# POWERSYSTEM.net
KiCad netlist of a schematic drawn in Altium Designer
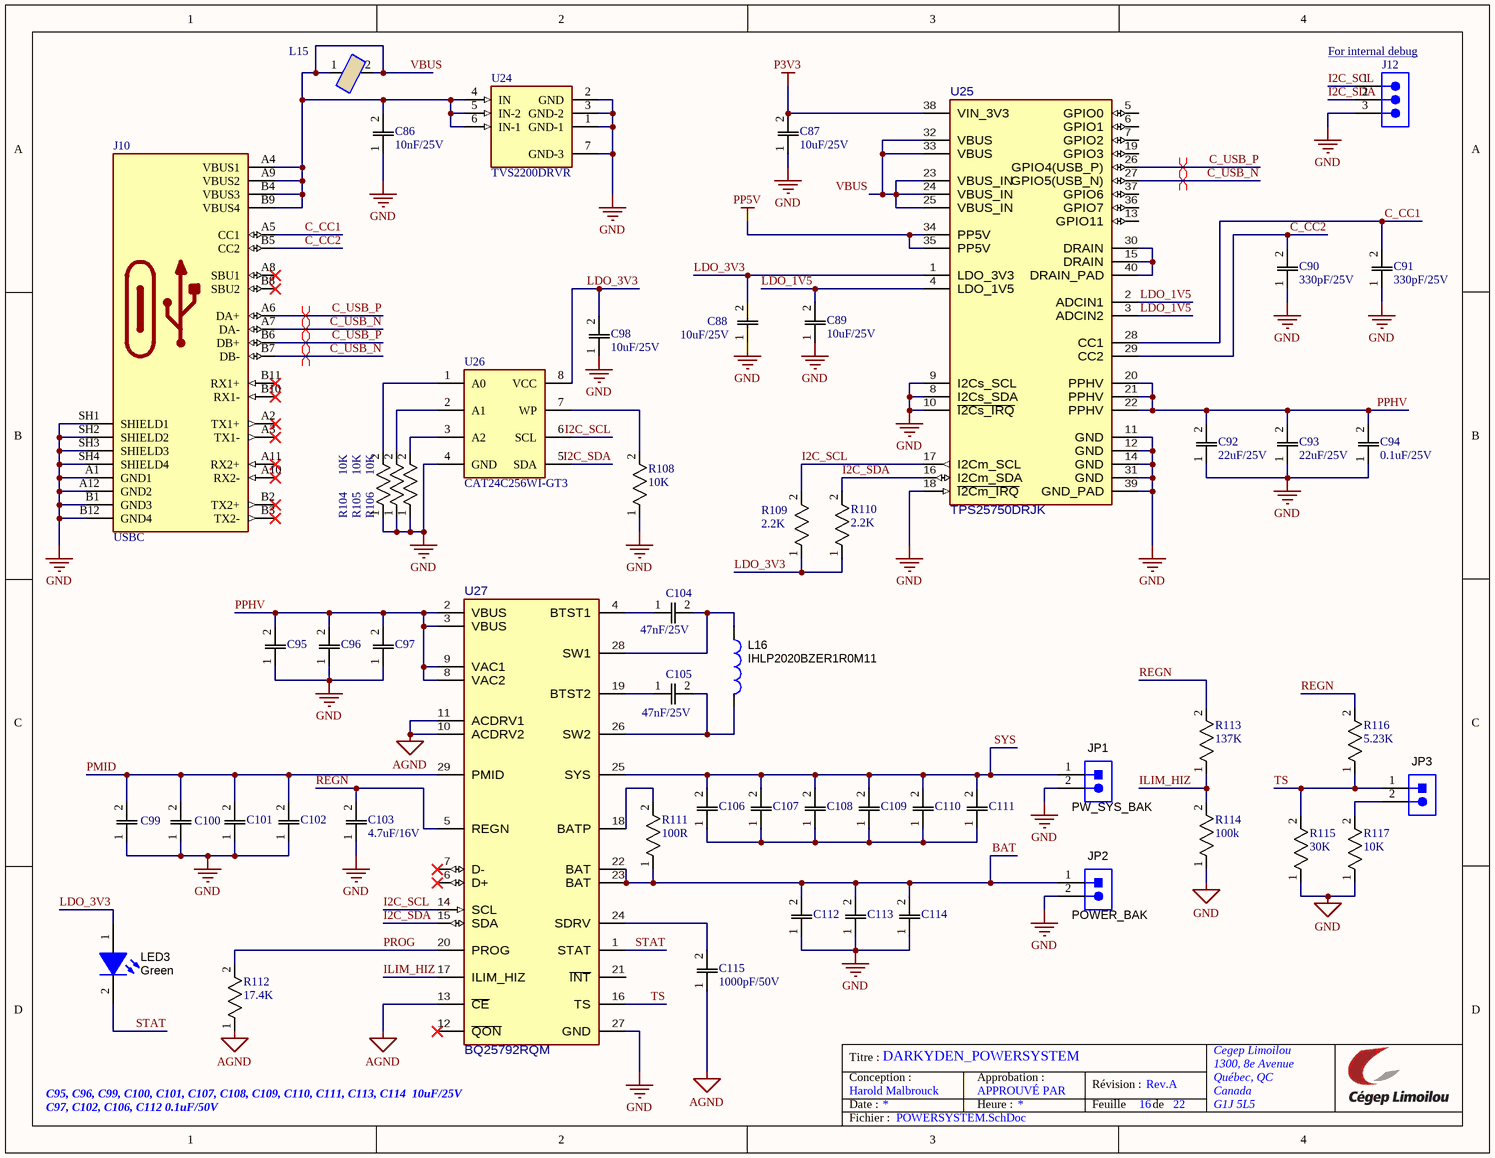
[diagram p0: POWERSYSTEM.SchDoc]

(export (version "E")
  (design (tool "Eeschema 10.0.6"))
  (components
    (comp (ref "C86")
      (value "10nF/25V")
      (footprint "CAPC220145_88N_KEM")
      (description "No Description Available")
      (libsource (lib "Capacitor_0805") (part "Capacitor_0805"))
    )
    (comp (ref "C87")
      (value "10uF/25V")
      (footprint "CAPC220145_88N_KEM")
      (description "No Description Available")
      (libsource (lib "Capacitor_0805") (part "Capacitor_0805"))
    )
    (comp (ref "C88")
      (value "10uF/25V")
      (footprint "CAPC220145_88N_KEM")
      (description "No Description Available")
      (libsource (lib "Capacitor_0805") (part "Capacitor_0805"))
    )
    (comp (ref "C89")
      (value "10uF/25V")
      (footprint "CAPC220145_88N_KEM")
      (description "No Description Available")
      (libsource (lib "Capacitor_0805") (part "Capacitor_0805"))
    )
    (comp (ref "C90")
      (value "330pF/25V")
      (footprint "CAPC220145_88N_KEM")
      (description "No Description Available")
      (libsource (lib "Capacitor_0805") (part "Capacitor_0805"))
    )
    (comp (ref "C91")
      (value "330pF/25V")
      (footprint "CAPC220145_88N_KEM")
      (description "No Description Available")
      (libsource (lib "Capacitor_0805") (part "Capacitor_0805"))
    )
    (comp (ref "C92")
      (value "22uF/25V")
      (footprint "CAPC220145_88N_KEM")
      (description "No Description Available")
      (libsource (lib "Capacitor_0805") (part "Capacitor_0805"))
    )
    (comp (ref "C93")
      (value "22uF/25V")
      (footprint "CAPC220145_88N_KEM")
      (description "No Description Available")
      (libsource (lib "Capacitor_0805") (part "Capacitor_0805"))
    )
    (comp (ref "C94")
      (value "0.1uF/25V")
      (footprint "CAPC220145_88N_KEM")
      (description "No Description Available")
      (libsource (lib "Capacitor_0805") (part "Capacitor_0805"))
    )
    (comp (ref "C95")
      (value "10uF/25V")
      (footprint "CAPC220145_88N_KEM")
      (description "No Description Available")
      (libsource (lib "Capacitor_0805") (part "Capacitor_0805"))
    )
    (comp (ref "C96")
      (value "10uF/25V")
      (footprint "CAPC220145_88N_KEM")
      (description "No Description Available")
      (libsource (lib "Capacitor_0805") (part "Capacitor_0805"))
    )
    (comp (ref "C97")
      (value "0.1uF/50V")
      (footprint "CAPC220145_88N_KEM")
      (description "No Description Available")
      (libsource (lib "Capacitor_0805") (part "Capacitor_0805"))
    )
    (comp (ref "C98")
      (value "10uF/25V")
      (footprint "CAPC220145_88N_KEM")
      (description "No Description Available")
      (libsource (lib "Capacitor_0805") (part "Capacitor_0805"))
    )
    (comp (ref "C99")
      (value "10uF/25V")
      (footprint "CAPC220145_88N_KEM")
      (description "No Description Available")
      (libsource (lib "Capacitor_0805") (part "Capacitor_0805"))
    )
    (comp (ref "C100")
      (value "10uF/25V")
      (footprint "CAPC220145_88N_KEM")
      (description "No Description Available")
      (libsource (lib "Capacitor_0805") (part "Capacitor_0805"))
    )
    (comp (ref "C101")
      (value "10uF/25V")
      (footprint "CAPC220145_88N_KEM")
      (description "No Description Available")
      (libsource (lib "Capacitor_0805") (part "Capacitor_0805"))
    )
    (comp (ref "C102")
      (value "0.1uF/50V")
      (footprint "CAPC220145_88N_KEM")
      (description "No Description Available")
      (libsource (lib "Capacitor_0805") (part "Capacitor_0805"))
    )
    (comp (ref "C103")
      (value "4.7uF/16V")
      (footprint "CAPC220145_88N_KEM")
      (description "No Description Available")
      (libsource (lib "Capacitor_0805") (part "Capacitor_0805"))
    )
    (comp (ref "C104")
      (value "47nF/25V")
      (footprint "CAPC220145_88N_KEM")
      (description "No Description Available")
      (libsource (lib "Capacitor_0805") (part "Capacitor_0805"))
    )
    (comp (ref "C105")
      (value "47nF/25V")
      (footprint "CAPC220145_88N_KEM")
      (description "No Description Available")
      (libsource (lib "Capacitor_0805") (part "Capacitor_0805"))
    )
    (comp (ref "C106")
      (value "0.1uF/50V")
      (footprint "CAPC220145_88N_KEM")
      (description "No Description Available")
      (libsource (lib "Capacitor_0805") (part "Capacitor_0805"))
    )
    (comp (ref "C107")
      (value "10uF/25V")
      (footprint "CAPC220145_88N_KEM")
      (description "No Description Available")
      (libsource (lib "Capacitor_0805") (part "Capacitor_0805"))
    )
    (comp (ref "C108")
      (value "10uF/25V")
      (footprint "CAPC220145_88N_KEM")
      (description "No Description Available")
      (libsource (lib "Capacitor_0805") (part "Capacitor_0805"))
    )
    (comp (ref "C109")
      (value "10uF/25V")
      (footprint "CAPC220145_88N_KEM")
      (description "No Description Available")
      (libsource (lib "Capacitor_0805") (part "Capacitor_0805"))
    )
    (comp (ref "C110")
      (value "10uF/25V")
      (footprint "CAPC220145_88N_KEM")
      (description "No Description Available")
      (libsource (lib "Capacitor_0805") (part "Capacitor_0805"))
    )
    (comp (ref "C111")
      (value "10uF/25V")
      (footprint "CAPC220145_88N_KEM")
      (description "No Description Available")
      (libsource (lib "Capacitor_0805") (part "Capacitor_0805"))
    )
    (comp (ref "C112")
      (value "0.1uF/50V")
      (footprint "CAPC220145_88N_KEM")
      (description "No Description Available")
      (libsource (lib "Capacitor_0805") (part "Capacitor_0805"))
    )
    (comp (ref "C113")
      (value "10uF/25V")
      (footprint "CAPC220145_88N_KEM")
      (description "No Description Available")
      (libsource (lib "Capacitor_0805") (part "Capacitor_0805"))
    )
    (comp (ref "C114")
      (value "10uF/25V")
      (footprint "CAPC220145_88N_KEM")
      (description "No Description Available")
      (libsource (lib "Capacitor_0805") (part "Capacitor_0805"))
    )
    (comp (ref "C115")
      (value "1000pF/50V")
      (footprint "CAPC220145_88N_KEM")
      (description "No Description Available")
      (libsource (lib "Capacitor_0805") (part "Capacitor_0805"))
    )
    (comp (ref "J10")
      (value "USBC")
      (footprint "MOLEX_2012670005")
      (fields (field (name "MF") "Molex") (field (name "MP") "2012670005"))
      (libsource (lib "USBC") (part "USBC"))
    )
    (comp (ref "J12")
      (value "61300311121")
      (footprint "61300311121")
      (description "WR-PHD Pin Header, THT, Vertical, pitch 2.54mm, 1 Row, 3P")
      (fields (field (name "MANUFACTURER") "Wurth Elektronik"))
      (libsource (lib "Header") (part "61300311121"))
    )
    (comp (ref "JP1")
      (value "PW_SYS_BAK")
      (footprint "61300211121")
      (description "Header, 100mil, 2x1, Tin, TH")
      (fields
        (field (name "PARTNUMBER") "PEC02SAAN")
        (field (name "MANUFACTURER") "Sullins Connector Solutions")
        (field (name "PUBLISHER") "Texas Instruments")
      )
      (libsource (lib "texas_instrument_power") (part "Header_2x1"))
    )
    (comp (ref "JP2")
      (value "POWER_BAK")
      (footprint "61300211121")
      (description "Header, 100mil, 2x1, Tin, TH")
      (fields
        (field (name "PARTNUMBER") "PEC02SAAN")
        (field (name "MANUFACTURER") "Sullins Connector Solutions")
        (field (name "PUBLISHER") "Texas Instruments")
      )
      (libsource (lib "texas_instrument_power") (part "Header_2x1"))
    )
    (comp (ref "JP3")
      (value "TS")
      (footprint "61300211121")
      (description "Header, 100mil, 2x1, Tin, TH")
      (fields
        (field (name "PARTNUMBER") "PEC02SAAN")
        (field (name "MANUFACTURER") "Sullins Connector Solutions")
        (field (name "PUBLISHER") "Texas Instruments")
      )
      (libsource (lib "texas_instrument_power") (part "Header_2x1"))
    )
    (comp (ref "L15")
      (value "FBMJ2125HM210NT")
      (footprint "INDC2012X105N")
      (description "Ferrite Beads Power Chip 21Ohm 30% 100MHz 6A 0.004Ohm DCR 0805 Automotive T/R")
      (fields
        (field (name "MANUFACTURER") "Taiyo Yuden")
        (field (name "MOUSER PART NUMBER") "963-FBMJ2125HM210NT")
      )
      (libsource (lib "SamacSys") (part "FBMJ2125HM210NT"))
    )
    (comp (ref "L16")
      (value "IHLP2020BZER1R0M11")
      (footprint "IHLP-2020BZ")
      (description "Inductor, Shielded Drum Core, Powdered Iron, 1 uH, 7 A, 0.0181 ohm, SMD")
      (fields (field (name "MANUFACTURER") "Vishay-Dale") (field (name "PUBLISHER") "Texas Instruments"))
      (libsource (lib "texas_instrument_power") (part "IHLP2020BZER1R0M11"))
    )
    (comp (ref "LED3")
      (value "Green")
      (footprint "LED_LTST-C190")
      (description "LED, Green, SMD")
      (fields (field (name "MANUFACTURER") "Lite-On") (field (name "PARTNUMBER") "LTST-C190GKT"))
      (libsource (lib "PD_BQ_Ref_Design") (part "LED_Gr_SMD"))
    )
    (comp (ref "R104")
      (value "10K")
      (footprint "SamacSys:ERJ3EKF1000V")
      (description "10K Ohm 5% Res Thick Film 0603  0.1W(1/10W) ±200ppm/C Pad SMD Automotive T/R")
      (fields
        (field (name "MANUFACTURER_PART_NUMBER") "ERJ-3GEYJ103V")
        (field (name "MOUSER PART NUMBER") "667-ERJ-3GEYJ103V")
      )
      (libsource (lib "SamacSys") (part "ERJ-3GEYJ103V"))
    )
    (comp (ref "R105")
      (value "10K")
      (footprint "SamacSys:ERJ3EKF1000V")
      (description "10K Ohm 5% Res Thick Film 0603  0.1W(1/10W) ±200ppm/C Pad SMD Automotive T/R")
      (fields
        (field (name "MANUFACTURER_PART_NUMBER") "ERJ-3GEYJ103V")
        (field (name "MOUSER PART NUMBER") "667-ERJ-3GEYJ103V")
      )
      (libsource (lib "SamacSys") (part "ERJ-3GEYJ103V"))
    )
    (comp (ref "R106")
      (value "10K")
      (footprint "SamacSys:ERJ3EKF1000V")
      (description "10K Ohm 5% Res Thick Film 0603  0.1W(1/10W) ±200ppm/C Pad SMD Automotive T/R")
      (fields
        (field (name "MANUFACTURER_PART_NUMBER") "ERJ-3GEYJ103V")
        (field (name "MOUSER PART NUMBER") "667-ERJ-3GEYJ103V")
      )
      (libsource (lib "SamacSys") (part "ERJ-3GEYJ103V"))
    )
    (comp (ref "R108")
      (value "10K")
      (footprint "SamacSys:ERJ3EKF1000V")
      (description "10K Ohm 5% Res Thick Film 0603  0.1W(1/10W) ±200ppm/C Pad SMD Automotive T/R")
      (fields
        (field (name "MANUFACTURER_PART_NUMBER") "ERJ-3GEYJ103V")
        (field (name "MOUSER PART NUMBER") "667-ERJ-3GEYJ103V")
      )
      (libsource (lib "SamacSys") (part "ERJ-3GEYJ103V"))
    )
    (comp (ref "R109")
      (value "2.2K")
      (footprint "SamacSys:ERJ3EKF1000V")
      (description "2.2 kOhm, ï¿½ 5%, 100 mW, 0603 [1608 Metric], Thick Film, General Purpose")
      (fields
        (field (name "MANUFACTURER_PART_NUMBER") "ERJ-3GEYJ222V")
        (field (name "MOUSER PART NUMBER") "667-ERJ-3GEYJ222V")
      )
      (libsource (lib "SamacSys") (part "ERJ-3GEYJ222V"))
    )
    (comp (ref "R110")
      (value "2.2K")
      (footprint "SamacSys:ERJ3EKF1000V")
      (description "2.2 kOhm, ï¿½ 5%, 100 mW, 0603 [1608 Metric], Thick Film, General Purpose")
      (fields
        (field (name "MANUFACTURER_PART_NUMBER") "ERJ-3GEYJ222V")
        (field (name "MOUSER PART NUMBER") "667-ERJ-3GEYJ222V")
      )
      (libsource (lib "SamacSys") (part "ERJ-3GEYJ222V"))
    )
    (comp (ref "R111")
      (value "100R")
      (footprint "SamacSys:RESC1608X55N")
      (description "100 Ohm 1% 1/10W 0603 ±100ppm/°C Molded SMD Punched Carrier T/R")
      (fields
        (field (name "MANUFACTURER_PART_NUMBER") "ERJ-3EKF1000V")
        (field (name "MOUSER PART NUMBER") "667-ERJ-3EKF1000V")
      )
      (libsource (lib "SamacSys") (part "ERJ-3EKF1000V"))
    )
    (comp (ref "R112")
      (value "17.4K")
      (footprint "SamacSys:RESC1608X55N")
      (description "17.4K Ohm 1% 1/10W +/-100ppm/ßC Molded Res Thick Film 0603  SMD Punched Carrier T/R")
      (fields
        (field (name "MANUFACTURER_PART_NUMBER") "ERJ-3EKF1742V")
        (field (name "MOUSER PART NUMBER") "667-ERJ-3EKF1742V")
      )
      (libsource (lib "SamacSys") (part "ERJ-3EKF1742V"))
    )
    (comp (ref "R113")
      (value "137K")
      (footprint "SamacSys:RESC1608X55N")
      (description "137K Ohm 1% 1/10W Res Thick Film 0603 ±100ppm/°C SMD Punched Carrier T/R")
      (fields
        (field (name "MANUFACTURER_PART_NUMBER") "ERJ-3EKF1373V")
        (field (name "MOUSER PART NUMBER") "667-ERJ-3EKF1373V")
      )
      (libsource (lib "SamacSys") (part "ERJ-3EKF1373V"))
    )
    (comp (ref "R114")
      (value "100k")
      (footprint "SamacSys:ERJ3EKF1000V")
      (description "100K Ohm 5%  Res Thick Film 0603 1/10W +/-200ppm/ßC Molded SMD Punched Carrier T/R")
      (fields
        (field (name "MANUFACTURER_PART_NUMBER") "ERJ-3GEYJ104V")
        (field (name "MOUSER PART NUMBER") "667-ERJ-3GEYJ104V")
      )
      (libsource (lib "SamacSys") (part "ERJ-3GEYJ104V"))
    )
    (comp (ref "R115")
      (value "30K")
      (footprint "SamacSys:ERJ3EKF1000V")
      (description "30K Ohm 5% 0.1W(1/10W) +/-200ppm/ßC Res Thick Film 0603  SMD Automotive T/R")
      (fields
        (field (name "MANUFACTURER_PART_NUMBER") "ERJ-3GEYJ303V")
        (field (name "MOUSER PART NUMBER") "667-ERJ-3GEYJ303V")
      )
      (libsource (lib "SamacSys") (part "ERJ-3GEYJ303V"))
    )
    (comp (ref "R116")
      (value "5.23K")
      (footprint "SamacSys:RESC1608X55N")
      (description "5.23K Ohm 1% 1/10W Res Thick Film 0603+/-100ppm/ßC Molded SMD Punched Carrier T/R")
      (fields
        (field (name "MANUFACTURER_PART_NUMBER") "ERJ-3EKF5231V")
        (field (name "MOUSER PART NUMBER") "667-ERJ-3EKF5231V")
      )
      (libsource (lib "SamacSys") (part "ERJ-3EKF5231V"))
    )
    (comp (ref "R117")
      (value "10K")
      (footprint "SamacSys:ERJ3EKF1000V")
      (description "10K Ohm 5% Res Thick Film 0603  0.1W(1/10W) ±200ppm/C Pad SMD Automotive T/R")
      (fields
        (field (name "MANUFACTURER_PART_NUMBER") "ERJ-3GEYJ103V")
        (field (name "MOUSER PART NUMBER") "667-ERJ-3GEYJ103V")
      )
      (libsource (lib "SamacSys") (part "ERJ-3GEYJ103V"))
    )
    (comp (ref "U24")
      (value "TVS2200DRVR")
      (footprint "SON65P200X200X80-7N")
      (description "ESD Suppressors / TVS Diodes 22V flat-clamp surge protection device 6-WSON -40 to 125")
      (fields (field (name "MF") "Texas Instruments"))
      (libsource (lib "TVS2200") (part "TVS2200DRVR"))
    )
    (comp (ref "U25")
      (value "TPS25750DRJK")
      (footprint "RJK0038B-C01-MFG")
      (description "USB Type-C and USB PD Controller with Integrated Power Switches Optimized for Power Applications")
      (fields (field (name "MANUFACTURER") "Texas Instruments"))
      (libsource (lib "PD_BQ_Ref_Design") (part "TPS25750DRJK"))
    )
    (comp (ref "U26")
      (value "CAT24C256WI-GT3")
      (footprint "SamacSys:SOIC127P600X175-8N")
      (description "EEPROM Memory IC 256Kbit I2C 1 MHz 500 ns 8-SOIC")
      (fields (field (name "MOUSER PART NUMBER") "698-CAT24C256WI-GT3"))
      (libsource (lib "SamacSys") (part "CAT24C256WI-GT3"))
    )
    (comp (ref "U27")
      (value "BQ25792RQM")
      (footprint "RQM0029A-MFG")
      (description "BQ2579x HotRod")
      (fields (field (name "MANUFACTURER") "Texas Instruments"))
      (libsource (lib "PD_BQ_Ref_Design") (part "BQ2579x"))
    )
  )
  (nets
    (net (code "1") (name "/BAT") (class "Default")
      (node (ref "C112") (pin "2") (pinfunction "2_2") (pintype "passive"))
      (node (ref "C113") (pin "2") (pinfunction "2_2") (pintype "passive"))
      (node (ref "C114") (pin "2") (pinfunction "2_2") (pintype "passive"))
      (node (ref "JP2") (pin "1") (pinfunction "1_1") (pintype "passive"))
      (node (ref "R111") (pin "1") (pinfunction "1_1") (pintype "passive"))
      (node (ref "U27") (pin "22") (pinfunction "BAT_22") (pintype "passive"))
      (node (ref "U27") (pin "23") (pinfunction "BAT_23") (pintype "passive"))
    )
    (net (code "2") (name "/C_CC1") (class "Default")
      (node (ref "C91") (pin "2") (pinfunction "2_2") (pintype "passive"))
      (node (ref "J10") (pin "A5") (pinfunction "CC1_A5") (pintype "bidirectional"))
      (node (ref "U25") (pin "28") (pinfunction "CC1_28") (pintype "passive"))
    )
    (net (code "3") (name "/C_CC2") (class "Default")
      (node (ref "C90") (pin "2") (pinfunction "2_2") (pintype "passive"))
      (node (ref "J10") (pin "B5") (pinfunction "CC2_B5") (pintype "bidirectional"))
      (node (ref "U25") (pin "29") (pinfunction "CC2_29") (pintype "passive"))
    )
    (net (code "4") (name "/C_USB_N") (class "Default")
      (node (ref "J10") (pin "A7") (pinfunction "DA-_A7") (pintype "bidirectional"))
      (node (ref "J10") (pin "B7") (pinfunction "DB-_B7") (pintype "bidirectional"))
      (node (ref "U25") (pin "27") (pinfunction "GPIO5(USB_N)_27") (pintype "bidirectional"))
    )
    (net (code "5") (name "/C_USB_P") (class "Default")
      (node (ref "J10") (pin "A6") (pinfunction "DA+_A6") (pintype "bidirectional"))
      (node (ref "J10") (pin "B6") (pinfunction "DB+_B6") (pintype "bidirectional"))
      (node (ref "U25") (pin "26") (pinfunction "GPIO4(USB_P)_26") (pintype "bidirectional"))
    )
    (net (code "6") (name "/I2C_SCL") (class "Default")
      (node (ref "J12") (pin "1") (pinfunction "1_1") (pintype "passive"))
      (node (ref "R109") (pin "2") (pinfunction "2_2") (pintype "passive"))
      (node (ref "U25") (pin "17") (pinfunction "I2Cm_SCL_17") (pintype "output"))
      (node (ref "U26") (pin "6") (pinfunction "SCL_6") (pintype "passive"))
      (node (ref "U27") (pin "14") (pinfunction "SCL_14") (pintype "input"))
    )
    (net (code "7") (name "/I2C_SDA") (class "Default")
      (node (ref "J12") (pin "2") (pinfunction "2_2") (pintype "passive"))
      (node (ref "R110") (pin "2") (pinfunction "2_2") (pintype "passive"))
      (node (ref "U25") (pin "16") (pinfunction "I2Cm_SDA_16") (pintype "bidirectional"))
      (node (ref "U26") (pin "5") (pinfunction "SDA_5") (pintype "passive"))
      (node (ref "U27") (pin "15") (pinfunction "SDA_15") (pintype "bidirectional"))
    )
    (net (code "8") (name "/ILIM_HIZ") (class "Default")
      (node (ref "R113") (pin "1") (pinfunction "1_1") (pintype "passive"))
      (node (ref "R114") (pin "2") (pinfunction "2_2") (pintype "passive"))
      (node (ref "U27") (pin "17") (pinfunction "ILIM_HIZ_17") (pintype "passive"))
    )
    (net (code "9") (name "/LDO_1V5") (class "Default")
      (node (ref "C89") (pin "2") (pinfunction "2_2") (pintype "passive"))
      (node (ref "U25") (pin "2") (pinfunction "ADCIN1_2") (pintype "passive"))
      (node (ref "U25") (pin "3") (pinfunction "ADCIN2_3") (pintype "passive"))
      (node (ref "U25") (pin "4") (pinfunction "LDO_1V5_4") (pintype "passive"))
    )
    (net (code "10") (name "/LDO_3V3") (class "Default")
      (node (ref "C88") (pin "2") (pinfunction "2_2") (pintype "passive"))
      (node (ref "C98") (pin "2") (pinfunction "2_2") (pintype "passive"))
      (node (ref "LED3") (pin "1") (pinfunction "A_1") (pintype "passive"))
      (node (ref "R109") (pin "1") (pinfunction "1_1") (pintype "passive"))
      (node (ref "R110") (pin "1") (pinfunction "1_1") (pintype "passive"))
      (node (ref "U25") (pin "1") (pinfunction "LDO_3V3_1") (pintype "passive"))
      (node (ref "U26") (pin "8") (pinfunction "VCC_8") (pintype "passive"))
    )
    (net (code "11") (name "/PMID") (class "Default")
      (node (ref "C100") (pin "2") (pinfunction "2_2") (pintype "passive"))
      (node (ref "C101") (pin "2") (pinfunction "2_2") (pintype "passive"))
      (node (ref "C102") (pin "2") (pinfunction "2_2") (pintype "passive"))
      (node (ref "C99") (pin "2") (pinfunction "2_2") (pintype "passive"))
      (node (ref "U27") (pin "29") (pinfunction "PMID_29") (pintype "passive"))
    )
    (net (code "12") (name "/PPHV") (class "Default")
      (node (ref "C92") (pin "2") (pinfunction "2_2") (pintype "passive"))
      (node (ref "C93") (pin "2") (pinfunction "2_2") (pintype "passive"))
      (node (ref "C94") (pin "2") (pinfunction "2_2") (pintype "passive"))
      (node (ref "C95") (pin "2") (pinfunction "2_2") (pintype "passive"))
      (node (ref "C96") (pin "2") (pinfunction "2_2") (pintype "passive"))
      (node (ref "C97") (pin "2") (pinfunction "2_2") (pintype "passive"))
      (node (ref "U25") (pin "20") (pinfunction "PPHV_20") (pintype "passive"))
      (node (ref "U25") (pin "21") (pinfunction "PPHV_21") (pintype "passive"))
      (node (ref "U25") (pin "22") (pinfunction "PPHV_22") (pintype "passive"))
      (node (ref "U27") (pin "2") (pinfunction "VBUS_2") (pintype "power_in"))
      (node (ref "U27") (pin "3") (pinfunction "VBUS_3") (pintype "power_in"))
      (node (ref "U27") (pin "8") (pinfunction "VAC2_8") (pintype "power_in"))
      (node (ref "U27") (pin "9") (pinfunction "VAC1_9") (pintype "power_in"))
    )
    (net (code "13") (name "/PROG") (class "Default")
      (node (ref "R112") (pin "2") (pinfunction "2_2") (pintype "passive"))
      (node (ref "U27") (pin "20") (pinfunction "PROG_20") (pintype "passive"))
    )
    (net (code "14") (name "/REGN") (class "Default")
      (node (ref "C103") (pin "2") (pinfunction "2_2") (pintype "passive"))
      (node (ref "R113") (pin "2") (pinfunction "2_2") (pintype "passive"))
      (node (ref "R116") (pin "2") (pinfunction "2_2") (pintype "passive"))
      (node (ref "U27") (pin "5") (pinfunction "REGN_5") (pintype "passive"))
    )
    (net (code "15") (name "/STAT") (class "Default")
      (node (ref "LED3") (pin "2") (pinfunction "K_2") (pintype "passive"))
      (node (ref "U27") (pin "1") (pinfunction "STAT_1") (pintype "passive"))
    )
    (net (code "16") (name "/SYS") (class "Default")
      (node (ref "C106") (pin "2") (pinfunction "2_2") (pintype "passive"))
      (node (ref "C107") (pin "2") (pinfunction "2_2") (pintype "passive"))
      (node (ref "C108") (pin "2") (pinfunction "2_2") (pintype "passive"))
      (node (ref "C109") (pin "2") (pinfunction "2_2") (pintype "passive"))
      (node (ref "C110") (pin "2") (pinfunction "2_2") (pintype "passive"))
      (node (ref "C111") (pin "2") (pinfunction "2_2") (pintype "passive"))
      (node (ref "JP1") (pin "1") (pinfunction "1_1") (pintype "passive"))
      (node (ref "U27") (pin "25") (pinfunction "SYS_25") (pintype "passive"))
    )
    (net (code "17") (name "/TS") (class "Default")
      (node (ref "JP3") (pin "1") (pinfunction "1_1") (pintype "passive"))
      (node (ref "R115") (pin "2") (pinfunction "2_2") (pintype "passive"))
      (node (ref "R116") (pin "1") (pinfunction "1_1") (pintype "passive"))
      (node (ref "U27") (pin "16") (pinfunction "TS_16") (pintype "passive"))
    )
    (net (code "18") (name "/VBUS") (class "Default")
      (node (ref "C86") (pin "2") (pinfunction "2_2") (pintype "passive"))
      (node (ref "J10") (pin "A4") (pinfunction "VBUS1_A4") (pintype "power_in"))
      (node (ref "J10") (pin "A9") (pinfunction "VBUS2_A9") (pintype "power_in"))
      (node (ref "J10") (pin "B4") (pinfunction "VBUS3_B4") (pintype "power_in"))
      (node (ref "J10") (pin "B9") (pinfunction "VBUS4_B9") (pintype "power_in"))
      (node (ref "L15") (pin "1") (pinfunction "1_1") (pintype "passive"))
      (node (ref "L15") (pin "2") (pinfunction "2_2") (pintype "passive"))
      (node (ref "U24") (pin "4") (pinfunction "IN_4") (pintype "input"))
      (node (ref "U24") (pin "5") (pinfunction "IN-2_5") (pintype "input"))
      (node (ref "U24") (pin "6") (pinfunction "IN-1_6") (pintype "input"))
      (node (ref "U25") (pin "23") (pinfunction "VBUS_IN_23") (pintype "power_in"))
      (node (ref "U25") (pin "24") (pinfunction "VBUS_IN_24") (pintype "power_in"))
      (node (ref "U25") (pin "25") (pinfunction "VBUS_IN_25") (pintype "power_in"))
      (node (ref "U25") (pin "32") (pinfunction "VBUS_32") (pintype "power_in"))
      (node (ref "U25") (pin "33") (pinfunction "VBUS_33") (pintype "power_in"))
    )
    (net (code "19") (name "AGND") (class "Default")
      (node (ref "C115") (pin "1") (pinfunction "1_1") (pintype "passive"))
      (node (ref "R112") (pin "1") (pinfunction "1_1") (pintype "passive"))
      (node (ref "U27") (pin "10") (pinfunction "ACDRV2_10") (pintype "power_in"))
      (node (ref "U27") (pin "11") (pinfunction "ACDRV1_11") (pintype "power_in"))
      (node (ref "U27") (pin "13") (pinfunction "~{CE}_13") (pintype "passive"))
    )
    (net (code "20") (name "GND") (class "Default")
      (node (ref "C100") (pin "1") (pinfunction "1_1") (pintype "passive"))
      (node (ref "C101") (pin "1") (pinfunction "1_1") (pintype "passive"))
      (node (ref "C102") (pin "1") (pinfunction "1_1") (pintype "passive"))
      (node (ref "C103") (pin "1") (pinfunction "1_1") (pintype "passive"))
      (node (ref "C112") (pin "1") (pinfunction "1_1") (pintype "passive"))
      (node (ref "C113") (pin "1") (pinfunction "1_1") (pintype "passive"))
      (node (ref "C114") (pin "1") (pinfunction "1_1") (pintype "passive"))
      (node (ref "C86") (pin "1") (pinfunction "1_1") (pintype "passive"))
      (node (ref "C87") (pin "1") (pinfunction "1_1") (pintype "passive"))
      (node (ref "C88") (pin "1") (pinfunction "1_1") (pintype "passive"))
      (node (ref "C89") (pin "1") (pinfunction "1_1") (pintype "passive"))
      (node (ref "C90") (pin "1") (pinfunction "1_1") (pintype "passive"))
      (node (ref "C91") (pin "1") (pinfunction "1_1") (pintype "passive"))
      (node (ref "C92") (pin "1") (pinfunction "1_1") (pintype "passive"))
      (node (ref "C93") (pin "1") (pinfunction "1_1") (pintype "passive"))
      (node (ref "C94") (pin "1") (pinfunction "1_1") (pintype "passive"))
      (node (ref "C95") (pin "1") (pinfunction "1_1") (pintype "passive"))
      (node (ref "C96") (pin "1") (pinfunction "1_1") (pintype "passive"))
      (node (ref "C97") (pin "1") (pinfunction "1_1") (pintype "passive"))
      (node (ref "C98") (pin "1") (pinfunction "1_1") (pintype "passive"))
      (node (ref "C99") (pin "1") (pinfunction "1_1") (pintype "passive"))
      (node (ref "J10") (pin "A1") (pinfunction "GND1_A1") (pintype "passive"))
      (node (ref "J10") (pin "A12") (pinfunction "GND2_A12") (pintype "passive"))
      (node (ref "J10") (pin "B1") (pinfunction "GND3_B1") (pintype "passive"))
      (node (ref "J10") (pin "B12") (pinfunction "GND4_B12") (pintype "passive"))
      (node (ref "J10") (pin "SH1") (pinfunction "SHIELD1_SH1") (pintype "passive"))
      (node (ref "J10") (pin "SH2") (pinfunction "SHIELD2_SH2") (pintype "passive"))
      (node (ref "J10") (pin "SH3") (pinfunction "SHIELD3_SH3") (pintype "passive"))
      (node (ref "J10") (pin "SH4") (pinfunction "SHIELD4_SH4") (pintype "passive"))
      (node (ref "J12") (pin "3") (pinfunction "3_3") (pintype "passive"))
      (node (ref "JP1") (pin "2") (pinfunction "2_2") (pintype "passive"))
      (node (ref "JP2") (pin "2") (pinfunction "2_2") (pintype "passive"))
      (node (ref "R104") (pin "1") (pinfunction "1_1") (pintype "passive"))
      (node (ref "R105") (pin "1") (pinfunction "1_1") (pintype "passive"))
      (node (ref "R106") (pin "1") (pinfunction "1_1") (pintype "passive"))
      (node (ref "R108") (pin "1") (pinfunction "1_1") (pintype "passive"))
      (node (ref "R114") (pin "1") (pinfunction "1_1") (pintype "passive"))
      (node (ref "R115") (pin "1") (pinfunction "1_1") (pintype "passive"))
      (node (ref "R117") (pin "1") (pinfunction "1_1") (pintype "passive"))
      (node (ref "U24") (pin "1") (pinfunction "GND-1_1") (pintype "passive"))
      (node (ref "U24") (pin "2") (pinfunction "GND_2") (pintype "passive"))
      (node (ref "U24") (pin "3") (pinfunction "GND-2_3") (pintype "passive"))
      (node (ref "U24") (pin "7") (pinfunction "GND-3_7") (pintype "passive"))
      (node (ref "U25") (pin "10") (pinfunction "~{I2Cs_IRQ}_10") (pintype "passive"))
      (node (ref "U25") (pin "11") (pinfunction "GND_11") (pintype "passive"))
      (node (ref "U25") (pin "12") (pinfunction "GND_12") (pintype "passive"))
      (node (ref "U25") (pin "14") (pinfunction "GND_14") (pintype "passive"))
      (node (ref "U25") (pin "18") (pinfunction "~{I2Cm_IRQ}_18") (pintype "input"))
      (node (ref "U25") (pin "31") (pinfunction "GND_31") (pintype "passive"))
      (node (ref "U25") (pin "39") (pinfunction "GND_PAD_39") (pintype "passive"))
      (node (ref "U25") (pin "8") (pinfunction "I2Cs_SDA_8") (pintype "passive"))
      (node (ref "U25") (pin "9") (pinfunction "I2Cs_SCL_9") (pintype "passive"))
      (node (ref "U26") (pin "4") (pinfunction "GND_4") (pintype "passive"))
      (node (ref "U27") (pin "27") (pinfunction "GND_27") (pintype "power_in"))
    )
    (net (code "21") (name "Net-(C106-Pad1)") (class "Default")
      (node (ref "C106") (pin "1") (pinfunction "1_1") (pintype "passive"))
      (node (ref "C107") (pin "1") (pinfunction "1_1") (pintype "passive"))
      (node (ref "C108") (pin "1") (pinfunction "1_1") (pintype "passive"))
      (node (ref "C109") (pin "1") (pinfunction "1_1") (pintype "passive"))
      (node (ref "C110") (pin "1") (pinfunction "1_1") (pintype "passive"))
      (node (ref "C111") (pin "1") (pinfunction "1_1") (pintype "passive"))
    )
    (net (code "22") (name "Net-(JP3-Pad2)") (class "Default")
      (node (ref "JP3") (pin "2") (pinfunction "2_2") (pintype "passive"))
      (node (ref "R117") (pin "2") (pinfunction "2_2") (pintype "passive"))
    )
    (net (code "23") (name "Net-(U25-DRAIN_PAD)") (class "Default")
      (node (ref "U25") (pin "15") (pinfunction "DRAIN_15") (pintype "passive"))
      (node (ref "U25") (pin "30") (pinfunction "DRAIN_30") (pintype "passive"))
      (node (ref "U25") (pin "40") (pinfunction "DRAIN_PAD_40") (pintype "passive"))
    )
    (net (code "24") (name "Net-(U26-A0)") (class "Default")
      (node (ref "R104") (pin "2") (pinfunction "2_2") (pintype "passive"))
      (node (ref "U26") (pin "1") (pinfunction "A0_1") (pintype "passive"))
    )
    (net (code "25") (name "Net-(U26-A1)") (class "Default")
      (node (ref "R105") (pin "2") (pinfunction "2_2") (pintype "passive"))
      (node (ref "U26") (pin "2") (pinfunction "A1_2") (pintype "passive"))
    )
    (net (code "26") (name "Net-(U26-A2)") (class "Default")
      (node (ref "R106") (pin "2") (pinfunction "2_2") (pintype "passive"))
      (node (ref "U26") (pin "3") (pinfunction "A2_3") (pintype "passive"))
    )
    (net (code "27") (name "Net-(U26-WP)") (class "Default")
      (node (ref "R108") (pin "2") (pinfunction "2_2") (pintype "passive"))
      (node (ref "U26") (pin "7") (pinfunction "WP_7") (pintype "passive"))
    )
    (net (code "28") (name "Net-(U27-BATP)") (class "Default")
      (node (ref "R111") (pin "2") (pinfunction "2_2") (pintype "passive"))
      (node (ref "U27") (pin "18") (pinfunction "BATP_18") (pintype "passive"))
    )
    (net (code "29") (name "Net-(U27-BTST1)") (class "Default")
      (node (ref "C104") (pin "1") (pinfunction "1_1") (pintype "passive"))
      (node (ref "U27") (pin "4") (pinfunction "BTST1_4") (pintype "passive"))
    )
    (net (code "30") (name "Net-(U27-BTST2)") (class "Default")
      (node (ref "C105") (pin "1") (pinfunction "1_1") (pintype "passive"))
      (node (ref "U27") (pin "19") (pinfunction "BTST2_19") (pintype "passive"))
    )
    (net (code "31") (name "Net-(U27-SDRV)") (class "Default")
      (node (ref "C115") (pin "2") (pinfunction "2_2") (pintype "passive"))
      (node (ref "U27") (pin "24") (pinfunction "SDRV_24") (pintype "passive"))
    )
    (net (code "32") (name "Net-(U27-SW1)") (class "Default")
      (node (ref "C104") (pin "2") (pinfunction "2_2") (pintype "passive"))
      (node (ref "L16") (pin "1") (pinfunction "1_1") (pintype "passive"))
      (node (ref "U27") (pin "28") (pinfunction "SW1_28") (pintype "passive"))
    )
    (net (code "33") (name "Net-(U27-SW2)") (class "Default")
      (node (ref "C105") (pin "2") (pinfunction "2_2") (pintype "passive"))
      (node (ref "L16") (pin "2") (pinfunction "2_2") (pintype "passive"))
      (node (ref "U27") (pin "26") (pinfunction "SW2_26") (pintype "passive"))
    )
    (net (code "34") (name "P3V3") (class "Default")
      (node (ref "C87") (pin "2") (pinfunction "2_2") (pintype "passive"))
      (node (ref "U25") (pin "38") (pinfunction "VIN_3V3_38") (pintype "power_in"))
    )
    (net (code "35") (name "PP5V") (class "Default")
      (node (ref "U25") (pin "34") (pinfunction "PP5V_34") (pintype "power_in"))
      (node (ref "U25") (pin "35") (pinfunction "PP5V_35") (pintype "power_in"))
    )
    (net (code "36") (name "unconnected-(J10-RX1+-PadB11)") (class "Default")
      (node (ref "J10") (pin "B11") (pinfunction "RX1+_B11") (pintype "input+no_connect"))
    )
    (net (code "37") (name "unconnected-(J10-RX1--PadB10)") (class "Default")
      (node (ref "J10") (pin "B10") (pinfunction "RX1-_B10") (pintype "input+no_connect"))
    )
    (net (code "38") (name "unconnected-(J10-RX2+-PadA11)") (class "Default")
      (node (ref "J10") (pin "A11") (pinfunction "RX2+_A11") (pintype "input+no_connect"))
    )
    (net (code "39") (name "unconnected-(J10-RX2--PadA10)") (class "Default")
      (node (ref "J10") (pin "A10") (pinfunction "RX2-_A10") (pintype "input+no_connect"))
    )
    (net (code "40") (name "unconnected-(J10-SBU1-PadA8)") (class "Default")
      (node (ref "J10") (pin "A8") (pinfunction "SBU1_A8") (pintype "bidirectional+no_connect"))
    )
    (net (code "41") (name "unconnected-(J10-SBU2-PadB8)") (class "Default")
      (node (ref "J10") (pin "B8") (pinfunction "SBU2_B8") (pintype "bidirectional+no_connect"))
    )
    (net (code "42") (name "unconnected-(J10-TX1+-PadA2)") (class "Default")
      (node (ref "J10") (pin "A2") (pinfunction "TX1+_A2") (pintype "output+no_connect"))
    )
    (net (code "43") (name "unconnected-(J10-TX1--PadA3)") (class "Default")
      (node (ref "J10") (pin "A3") (pinfunction "TX1-_A3") (pintype "output+no_connect"))
    )
    (net (code "44") (name "unconnected-(J10-TX2+-PadB2)") (class "Default")
      (node (ref "J10") (pin "B2") (pinfunction "TX2+_B2") (pintype "output+no_connect"))
    )
    (net (code "45") (name "unconnected-(J10-TX2--PadB3)") (class "Default")
      (node (ref "J10") (pin "B3") (pinfunction "TX2-_B3") (pintype "output+no_connect"))
    )
    (net (code "46") (name "unconnected-(U25-GPIO0-Pad5)") (class "Default")
      (node (ref "U25") (pin "5") (pinfunction "GPIO0_5") (pintype "bidirectional"))
    )
    (net (code "47") (name "unconnected-(U25-GPIO1-Pad6)") (class "Default")
      (node (ref "U25") (pin "6") (pinfunction "GPIO1_6") (pintype "bidirectional"))
    )
    (net (code "48") (name "unconnected-(U25-GPIO2-Pad7)") (class "Default")
      (node (ref "U25") (pin "7") (pinfunction "GPIO2_7") (pintype "bidirectional"))
    )
    (net (code "49") (name "unconnected-(U25-GPIO3-Pad19)") (class "Default")
      (node (ref "U25") (pin "19") (pinfunction "GPIO3_19") (pintype "bidirectional"))
    )
    (net (code "50") (name "unconnected-(U25-GPIO6-Pad37)") (class "Default")
      (node (ref "U25") (pin "37") (pinfunction "GPIO6_37") (pintype "bidirectional"))
    )
    (net (code "51") (name "unconnected-(U25-GPIO7-Pad36)") (class "Default")
      (node (ref "U25") (pin "36") (pinfunction "GPIO7_36") (pintype "bidirectional"))
    )
    (net (code "52") (name "unconnected-(U25-GPIO11-Pad13)") (class "Default")
      (node (ref "U25") (pin "13") (pinfunction "GPIO11_13") (pintype "bidirectional"))
    )
    (net (code "53") (name "unconnected-(U27-D+-Pad6)") (class "Default")
      (node (ref "U27") (pin "6") (pinfunction "D+_6") (pintype "bidirectional+no_connect"))
    )
    (net (code "54") (name "unconnected-(U27-D--Pad7)") (class "Default")
      (node (ref "U27") (pin "7") (pinfunction "D-_7") (pintype "bidirectional+no_connect"))
    )
    (net (code "55") (name "unconnected-(U27-~{INT}-Pad21)") (class "Default")
      (node (ref "U27") (pin "21") (pinfunction "~{INT}_21") (pintype "passive"))
    )
    (net (code "56") (name "unconnected-(U27-~{QON}-Pad12)") (class "Default")
      (node (ref "U27") (pin "12") (pinfunction "~{QON}_12") (pintype "passive+no_connect"))
    )
  )
)
